# 2_CircuitBreaker.net
KiCad netlist of a schematic drawn in Altium Designer
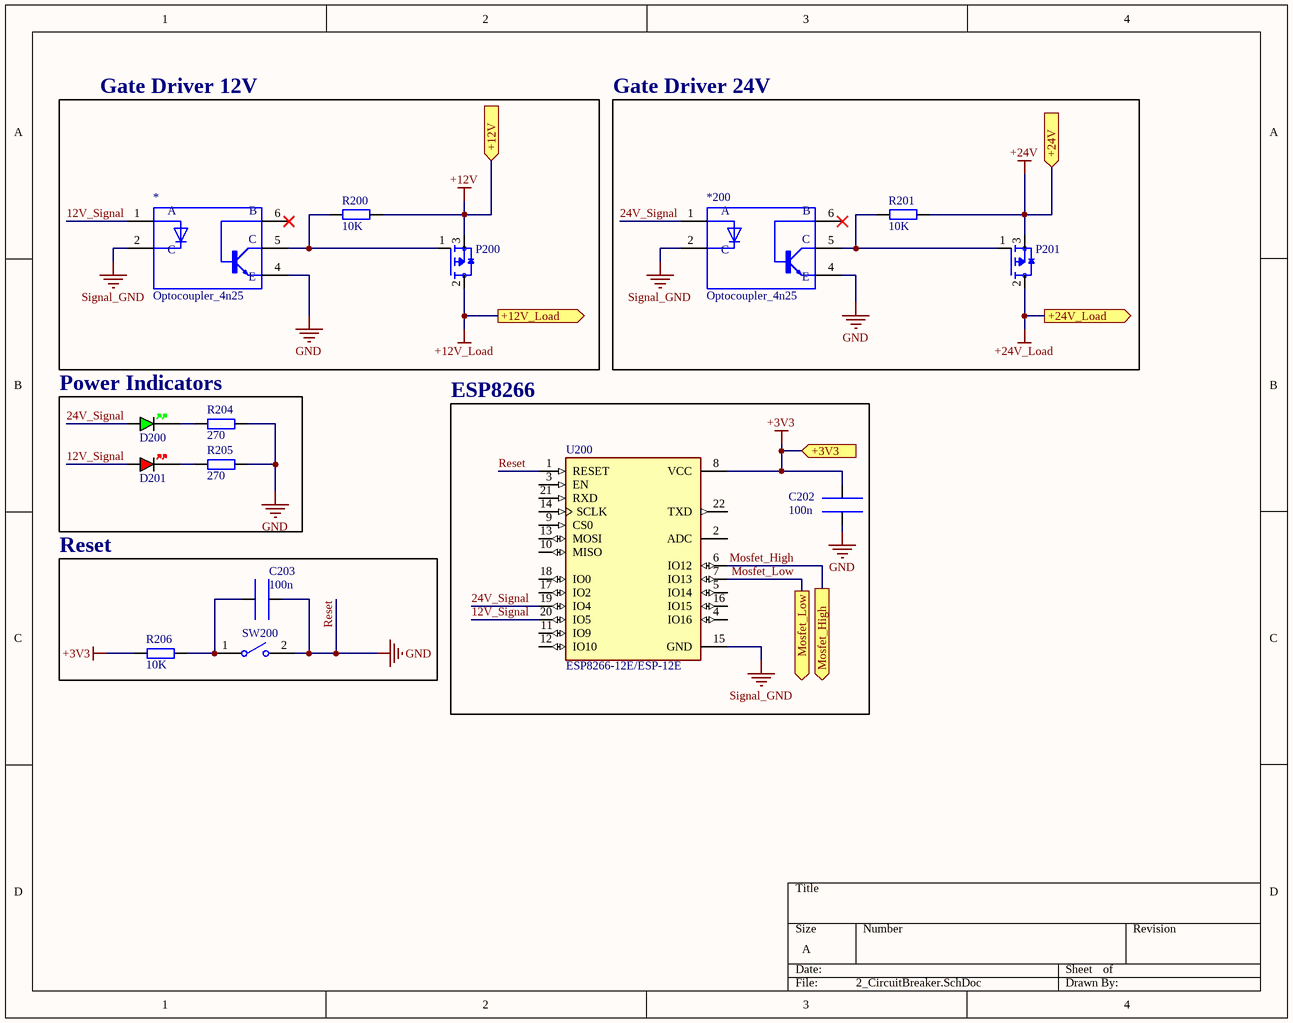
[diagram p0: 2_CircuitBreaker.SchDoc]

(export (version "E")
  (design (tool "Eeschema 10.0.6"))
  (components
    (comp (ref "*")
      (value "Optocoupler_4n25")
      (footprint "Optocoupler_4n25")
      (libsource (lib "MIA_LIBRARY") (part "Optocoupler_4n25"))
    )
    (comp (ref "*200")
      (value "Optocoupler_4n25")
      (footprint "Optocoupler_4n25")
      (libsource (lib "MIA_LIBRARY") (part "Optocoupler_4n25"))
    )
    (comp (ref "C202") (value "100n") (footprint "C0805") (libsource (lib "MIA_LIBRARY") (part "C0805")))
    (comp (ref "C203") (value "100n") (footprint "C0805") (libsource (lib "MIA_LIBRARY") (part "C0805")))
    (comp (ref "D200")
      (value "GREEN")
      (footprint "LED_0805_GREEN")
      (description "LED 0805 GREEN SMD")
      (libsource (lib "Schematic-Lib-PhilsLab") (part "LED_0805_GREEN"))
    )
    (comp (ref "D201")
      (value "RED")
      (footprint "LED_0603_RED")
      (description "LED 0603 RED SMD")
      (libsource (lib "Schematic-Lib-PhilsLab") (part "LED_0603_RED"))
    )
    (comp (ref "P200")
      (value "P Mosfet")
      (footprint "Mosfet")
      (libsource (lib "MIA_LIBRARY") (part "P Mosfet"))
    )
    (comp (ref "P201")
      (value "P Mosfet")
      (footprint "Mosfet")
      (libsource (lib "MIA_LIBRARY") (part "P Mosfet"))
    )
    (comp (ref "R200")
      (value "10K")
      (footprint "RES_1206")
      (description "Resistor SMD 1206")
      (libsource (lib "Schematic-Lib-PhilsLab") (part "RES_1206"))
    )
    (comp (ref "R201")
      (value "10K")
      (footprint "RES_1206")
      (description "Resistor SMD 1206")
      (libsource (lib "Schematic-Lib-PhilsLab") (part "RES_1206"))
    )
    (comp (ref "R204")
      (value "270")
      (footprint "RES_0805")
      (description "Resistor SMD 0805")
      (libsource (lib "Schematic-Lib-PhilsLab") (part "RES_0805"))
    )
    (comp (ref "R205")
      (value "270")
      (footprint "RES_0805")
      (description "Resistor SMD 0805")
      (libsource (lib "Schematic-Lib-PhilsLab") (part "RES_0805"))
    )
    (comp (ref "R206")
      (value "10K")
      (footprint "RES_1206")
      (description "Resistor SMD 1206")
      (libsource (lib "Schematic-Lib-PhilsLab") (part "RES_1206"))
    )
    (comp (ref "SW200")
      (value "~")
      (footprint "434121043816")
      (description "Switch Tactile Spst-no 0.05A 12V")
      (libsource (lib "Altium Content Vault") (part "SPST-NO_2P"))
    )
    (comp (ref "U200")
      (value "ESP8266-12E/ESP-12E")
      (footprint "XCVR_ESP8266-12E/ESP-12E")
      (fields (field (name "MF") "AI-Thinker"))
      (libsource (lib "ESP8266-12E_ESP-12E") (part "ESP8266-12E/ESP-12E"))
    )
  )
  (nets
    (net (code "1") (name "+3V3") (class "Default")
      (node (ref "C202") (pin "1") (pinfunction "1_1") (pintype "passive"))
      (node (ref "R206") (pin "2") (pinfunction "2_2") (pintype "passive"))
      (node (ref "U200") (pin "8") (pinfunction "VCC_8") (pintype "power_in"))
    )
    (net (code "2") (name "+12V") (class "Default")
      (node (ref "P200") (pin "3") (pinfunction "S_3") (pintype "passive"))
      (node (ref "R200") (pin "1") (pinfunction "1_1") (pintype "passive"))
    )
    (net (code "3") (name "+12V_Load") (class "Default")
      (node (ref "P200") (pin "2") (pinfunction "D_2") (pintype "passive"))
    )
    (net (code "4") (name "+24V") (class "Default")
      (node (ref "P201") (pin "3") (pinfunction "S_3") (pintype "passive"))
      (node (ref "R201") (pin "1") (pinfunction "1_1") (pintype "passive"))
    )
    (net (code "5") (name "+24V_Load") (class "Default")
      (node (ref "P201") (pin "2") (pinfunction "D_2") (pintype "passive"))
    )
    (net (code "6") (name "/12V_Signal") (class "Default")
      (node (ref "*") (pin "1") (pinfunction "A_1") (pintype "passive"))
      (node (ref "D201") (pin "A") (pinfunction "A_A") (pintype "passive"))
      (node (ref "U200") (pin "20") (pinfunction "IO5_20") (pintype "bidirectional"))
    )
    (net (code "7") (name "/24V_Signal") (class "Default")
      (node (ref "*200") (pin "1") (pinfunction "A_1") (pintype "passive"))
      (node (ref "D200") (pin "A") (pinfunction "A_A") (pintype "passive"))
      (node (ref "U200") (pin "19") (pinfunction "IO4_19") (pintype "bidirectional"))
    )
    (net (code "8") (name "/Mosfet_High") (class "Default")
      (node (ref "U200") (pin "6") (pinfunction "IO12_6") (pintype "bidirectional"))
    )
    (net (code "9") (name "/Mosfet_Low") (class "Default")
      (node (ref "U200") (pin "7") (pinfunction "IO13_7") (pintype "bidirectional"))
    )
    (net (code "10") (name "GND") (class "Default")
      (node (ref "*") (pin "4") (pinfunction "E_4") (pintype "passive"))
      (node (ref "*200") (pin "4") (pinfunction "E_4") (pintype "passive"))
      (node (ref "C202") (pin "1") (pinfunction "1_1") (pintype "passive"))
      (node (ref "C203") (pin "1") (pinfunction "1_1") (pintype "passive"))
      (node (ref "R204") (pin "2") (pinfunction "2_2") (pintype "passive"))
      (node (ref "R205") (pin "2") (pinfunction "2_2") (pintype "passive"))
      (node (ref "SW200") (pin "2") (pinfunction "2_2") (pintype "passive"))
      (node (ref "U200") (pin "1") (pinfunction "RESET_1") (pintype "input"))
    )
    (net (code "11") (name "Net-(*-C`)") (class "Default")
      (node (ref "*") (pin "5") (pinfunction "C`_5") (pintype "passive"))
      (node (ref "P200") (pin "1") (pinfunction "G_1") (pintype "passive"))
      (node (ref "R200") (pin "2") (pinfunction "2_2") (pintype "passive"))
    )
    (net (code "12") (name "Net-(*200-C`)") (class "Default")
      (node (ref "*200") (pin "5") (pinfunction "C`_5") (pintype "passive"))
      (node (ref "P201") (pin "1") (pinfunction "G_1") (pintype "passive"))
      (node (ref "R201") (pin "2") (pinfunction "2_2") (pintype "passive"))
    )
    (net (code "13") (name "Net-(C203-Pad1)") (class "Default")
      (node (ref "C203") (pin "1") (pinfunction "1_1") (pintype "passive"))
      (node (ref "R206") (pin "1") (pinfunction "1_1") (pintype "passive"))
      (node (ref "SW200") (pin "1") (pinfunction "1_1") (pintype "passive"))
    )
    (net (code "14") (name "Net-(D200-PadK)") (class "Default")
      (node (ref "D200") (pin "K") (pinfunction "K_K") (pintype "passive"))
      (node (ref "R204") (pin "1") (pinfunction "1_1") (pintype "passive"))
    )
    (net (code "15") (name "Net-(D201-PadK)") (class "Default")
      (node (ref "D201") (pin "K") (pinfunction "K_K") (pintype "passive"))
      (node (ref "R205") (pin "1") (pinfunction "1_1") (pintype "passive"))
    )
    (net (code "16") (name "Signal_GND") (class "Default")
      (node (ref "*") (pin "2") (pinfunction "C_2") (pintype "passive"))
      (node (ref "*200") (pin "2") (pinfunction "C_2") (pintype "passive"))
      (node (ref "U200") (pin "15") (pinfunction "GND_15") (pintype "power_in"))
    )
    (net (code "17") (name "unconnected-(*-B-Pad6)") (class "Default")
      (node (ref "*") (pin "6") (pinfunction "B_6") (pintype "passive+no_connect"))
    )
    (net (code "18") (name "unconnected-(*200-B-Pad6)") (class "Default")
      (node (ref "*200") (pin "6") (pinfunction "B_6") (pintype "passive+no_connect"))
    )
    (net (code "19") (name "unconnected-(U200-ADC-Pad2)") (class "Default")
      (node (ref "U200") (pin "2") (pinfunction "ADC_2") (pintype "passive"))
    )
    (net (code "20") (name "unconnected-(U200-CS0-Pad9)") (class "Default")
      (node (ref "U200") (pin "9") (pinfunction "CS0_9") (pintype "input"))
    )
    (net (code "21") (name "unconnected-(U200-EN-Pad3)") (class "Default")
      (node (ref "U200") (pin "3") (pinfunction "EN_3") (pintype "input"))
    )
    (net (code "22") (name "unconnected-(U200-IO0-Pad18)") (class "Default")
      (node (ref "U200") (pin "18") (pinfunction "IO0_18") (pintype "bidirectional"))
    )
    (net (code "23") (name "unconnected-(U200-IO2-Pad17)") (class "Default")
      (node (ref "U200") (pin "17") (pinfunction "IO2_17") (pintype "bidirectional"))
    )
    (net (code "24") (name "unconnected-(U200-IO9-Pad11)") (class "Default")
      (node (ref "U200") (pin "11") (pinfunction "IO9_11") (pintype "bidirectional"))
    )
    (net (code "25") (name "unconnected-(U200-IO10-Pad12)") (class "Default")
      (node (ref "U200") (pin "12") (pinfunction "IO10_12") (pintype "bidirectional"))
    )
    (net (code "26") (name "unconnected-(U200-IO14-Pad5)") (class "Default")
      (node (ref "U200") (pin "5") (pinfunction "IO14_5") (pintype "bidirectional"))
    )
    (net (code "27") (name "unconnected-(U200-IO15-Pad16)") (class "Default")
      (node (ref "U200") (pin "16") (pinfunction "IO15_16") (pintype "bidirectional"))
    )
    (net (code "28") (name "unconnected-(U200-IO16-Pad4)") (class "Default")
      (node (ref "U200") (pin "4") (pinfunction "IO16_4") (pintype "bidirectional"))
    )
    (net (code "29") (name "unconnected-(U200-MISO-Pad10)") (class "Default")
      (node (ref "U200") (pin "10") (pinfunction "MISO_10") (pintype "bidirectional"))
    )
    (net (code "30") (name "unconnected-(U200-MOSI-Pad13)") (class "Default")
      (node (ref "U200") (pin "13") (pinfunction "MOSI_13") (pintype "bidirectional"))
    )
    (net (code "31") (name "unconnected-(U200-RXD-Pad21)") (class "Default")
      (node (ref "U200") (pin "21") (pinfunction "RXD_21") (pintype "input"))
    )
    (net (code "32") (name "unconnected-(U200-SCLK-Pad14)") (class "Default")
      (node (ref "U200") (pin "14") (pinfunction "SCLK_14") (pintype "input"))
    )
    (net (code "33") (name "unconnected-(U200-TXD-Pad22)") (class "Default")
      (node (ref "U200") (pin "22") (pinfunction "TXD_22") (pintype "output"))
    )
  )
)
